# amplifier.net
KiCad netlist of a schematic drawn in EAGLE
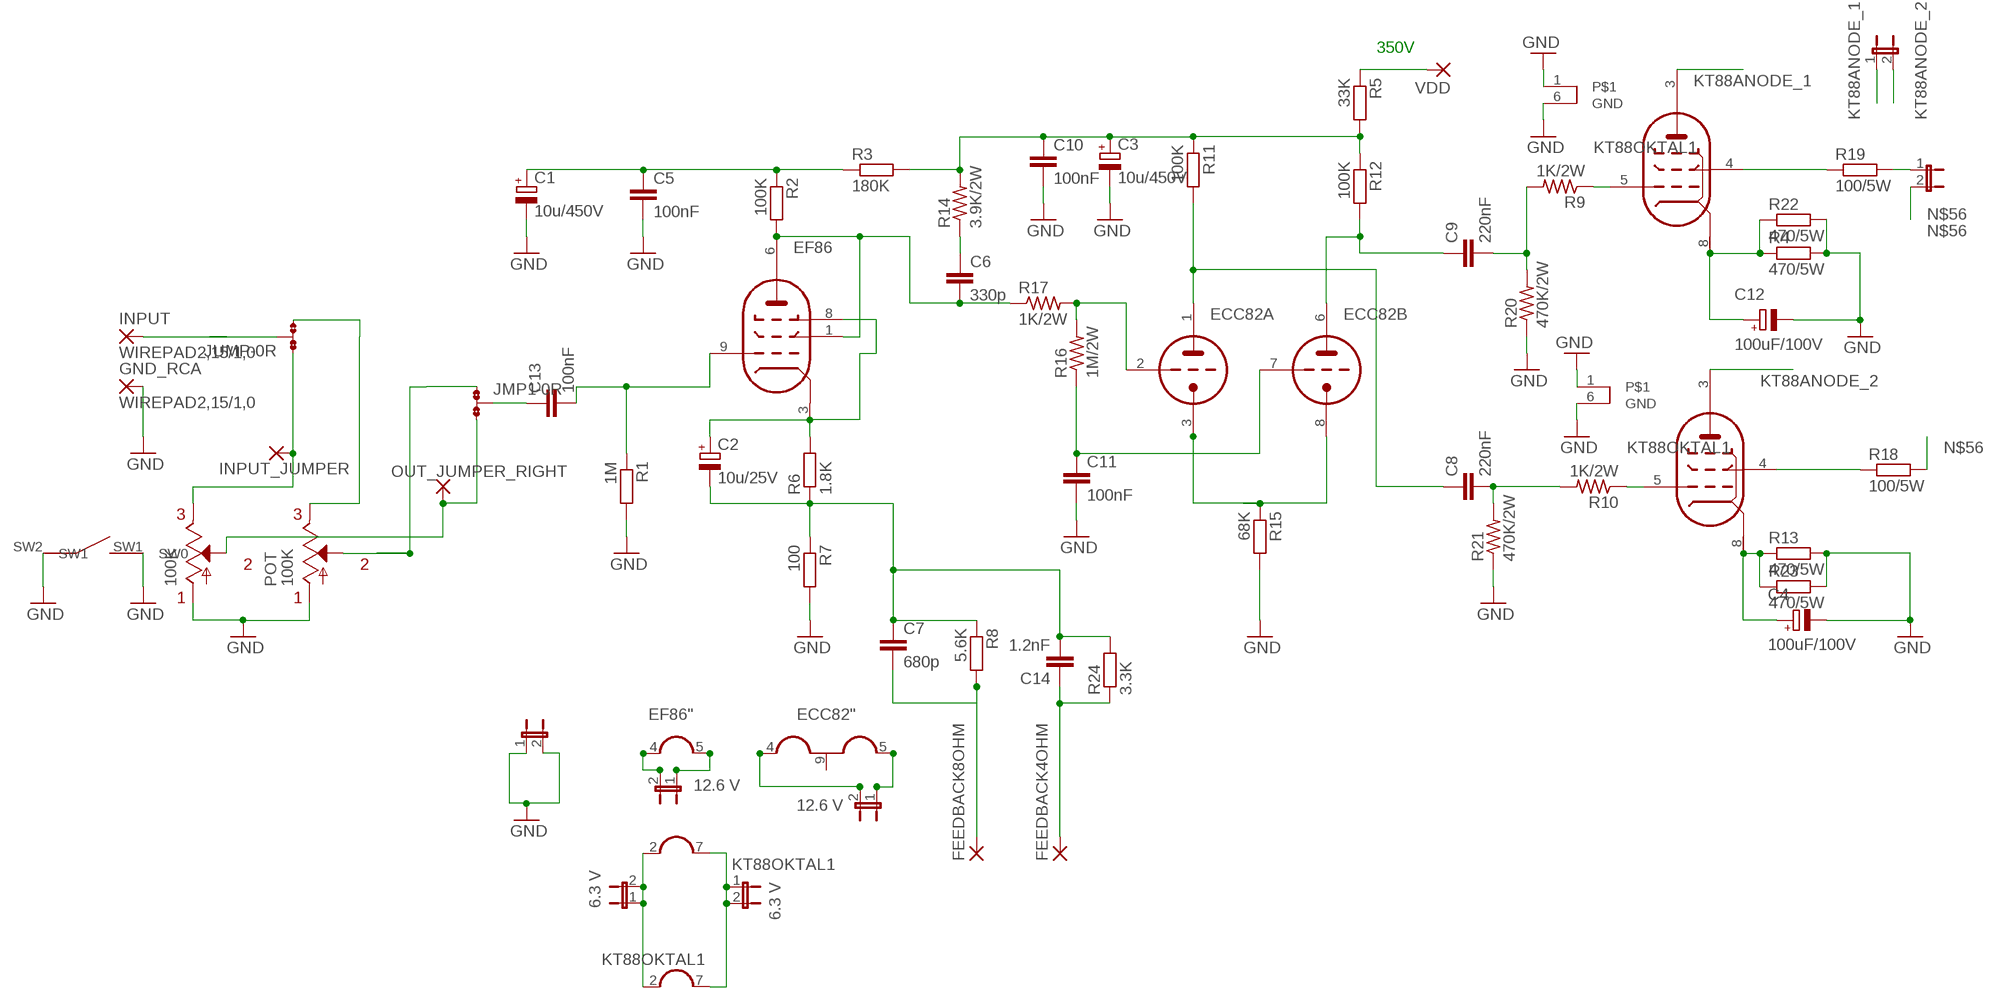
[diagram p0: schematic, sheet 1]

(export (version "E")
  (design (tool "Eeschema 10.0.6"))
  (components
    (comp (ref "6.3_KT88")
      (value "6.3 V")
      (footprint "eagle-import:JP1")
      (libsource (lib "eagle-import") (part "JP1E"))
    )
    (comp (ref "6.3_KTGND")
      (value "6.3 V")
      (footprint "eagle-import:JP1")
      (libsource (lib "eagle-import") (part "JP1E"))
    )
    (comp (ref "12.6V_ECC82")
      (value "12.6 V")
      (footprint "eagle-import:JP1")
      (libsource (lib "eagle-import") (part "JP1E"))
    )
    (comp (ref "12.6_EF86")
      (value "12.6 V")
      (footprint "eagle-import:JP1")
      (libsource (lib "eagle-import") (part "JP1E"))
    )
    (comp (ref "C1")
      (value "10u/450V")
      (footprint "eagle-import:E5-10,5")
      (libsource (lib "eagle-import") (part "CPOL-EUE5-10.5"))
    )
    (comp (ref "C2")
      (value "10u/25V")
      (footprint "eagle-import:E3,5-10")
      (libsource (lib "eagle-import") (part "CPOL-EUE3.5-10"))
    )
    (comp (ref "C3")
      (value "10u/450V")
      (footprint "eagle-import:E5-10,5")
      (libsource (lib "eagle-import") (part "CPOL-EUE5-10.5"))
    )
    (comp (ref "C4")
      (value "100uF/100V")
      (footprint "eagle-import:E3,5-10")
      (libsource (lib "eagle-import") (part "CPOL-EUE3.5-10"))
    )
    (comp (ref "C5")
      (value "100nF")
      (footprint "eagle-import:C7.5B3")
      (libsource (lib "eagle-import") (part "C7.5/3"))
    )
    (comp (ref "C6")
      (value "330p")
      (footprint "eagle-import:C5B5.5")
      (libsource (lib "eagle-import") (part "C5/5.5"))
    )
    (comp (ref "C7")
      (value "680p")
      (footprint "eagle-import:C5B5.5")
      (libsource (lib "eagle-import") (part "C5/5.5"))
    )
    (comp (ref "C8")
      (value "220nF")
      (footprint "eagle-import:C7.5B3")
      (libsource (lib "eagle-import") (part "C7.5/3"))
    )
    (comp (ref "C9")
      (value "220nF")
      (footprint "eagle-import:C7.5B3")
      (libsource (lib "eagle-import") (part "C7.5/3"))
    )
    (comp (ref "C10")
      (value "100nF")
      (footprint "eagle-import:C7.5B3")
      (libsource (lib "eagle-import") (part "C7.5/3"))
    )
    (comp (ref "C11")
      (value "100nF")
      (footprint "eagle-import:C7.5B3")
      (libsource (lib "eagle-import") (part "C7.5/3"))
    )
    (comp (ref "C12")
      (value "100uF/100V")
      (footprint "eagle-import:E3,5-10")
      (libsource (lib "eagle-import") (part "CPOL-EUE3.5-10"))
    )
    (comp (ref "C13")
      (value "100nF")
      (footprint "eagle-import:C0805K")
      (libsource (lib "eagle-import") (part "C-EUC0805K"))
    )
    (comp (ref "C14")
      (value "1.2nF")
      (footprint "eagle-import:C5B5.5")
      (libsource (lib "eagle-import") (part "C5/5.5"))
    )
    (comp (ref "ECC82")
      (value "ECC82-P")
      (footprint "eagle-import:NOVAL")
      (libsource (lib "eagle-import") (part "ECC82-P"))
    )
    (comp (ref "EF86")
      (value "EF86-P")
      (footprint "eagle-import:NOVAL")
      (libsource (lib "eagle-import") (part "EF86-P"))
    )
    (comp (ref "FEEDBACK4OHM")
      (value "2,54/1,1")
      (footprint "eagle-import:2,54_1,1")
      (libsource (lib "eagle-import") (part "2,54/1,1"))
    )
    (comp (ref "FEEDBACK8OHM")
      (value "2,54/1,1")
      (footprint "eagle-import:2,54_1,1")
      (libsource (lib "eagle-import") (part "2,54/1,1"))
    )
    (comp (ref "GND")
      (value "JP1E")
      (footprint "eagle-import:JP1")
      (libsource (lib "eagle-import") (part "JP1E"))
    )
    (comp (ref "GND_RCA")
      (value "WIREPAD2,15/1,0")
      (footprint "eagle-import:2,15_1,0")
      (libsource (lib "eagle-import") (part "WIREPAD2,15/1,0"))
    )
    (comp (ref "INPUT")
      (value "WIREPAD2,15/1,0")
      (footprint "eagle-import:2,15_1,0")
      (libsource (lib "eagle-import") (part "WIREPAD2,15/1,0"))
    )
    (comp (ref "INPUT_JUMPER")
      (value "2,54/1,1")
      (footprint "eagle-import:2,54_1,1")
      (libsource (lib "eagle-import") (part "2,54/1,1"))
    )
    (comp (ref "JMP1")
      (value "0R-JUMPA")
      (footprint "eagle-import:A0R-JMP")
      (libsource (lib "eagle-import") (part "0R-JUMPA"))
    )
    (comp (ref "JUMP")
      (value "0R-JUMPA")
      (footprint "eagle-import:A0R-JMP")
      (libsource (lib "eagle-import") (part "0R-JUMPA"))
    )
    (comp (ref "KT88_OUTPUT")
      (value "JP1E")
      (footprint "eagle-import:JP1")
      (libsource (lib "eagle-import") (part "JP1E"))
    )
    (comp (ref "KT88_TRAFO")
      (value "JP1E")
      (footprint "eagle-import:JP1")
      (libsource (lib "eagle-import") (part "JP1E"))
    )
    (comp (ref "OUT_JUMPER_RIGHT")
      (value "2,54/1,1")
      (footprint "eagle-import:2,54_1,1")
      (libsource (lib "eagle-import") (part "2,54/1,1"))
    )
    (comp (ref "POT")
      (value "100K")
      (footprint "eagle-import:PTR902-2015K-A104")
      (libsource (lib "eagle-import") (part "DUALPOTAUDIO"))
    )
    (comp (ref "R1")
      (value "1M")
      (footprint "eagle-import:R0805")
      (libsource (lib "eagle-import") (part "R-EU_R0805"))
    )
    (comp (ref "R2")
      (value "100K")
      (footprint "eagle-import:R0805")
      (libsource (lib "eagle-import") (part "R-EU_R0805"))
    )
    (comp (ref "R3")
      (value "180K")
      (footprint "eagle-import:R0805")
      (libsource (lib "eagle-import") (part "R-EU_R0805"))
    )
    (comp (ref "R4")
      (value "470/5W")
      (footprint "eagle-import:0617V")
      (libsource (lib "eagle-import") (part "resistor_mod_R-EU_0617/5V"))
    )
    (comp (ref "R5")
      (value "33K")
      (footprint "eagle-import:R0805")
      (libsource (lib "eagle-import") (part "R-EU_R0805"))
    )
    (comp (ref "R6")
      (value "1.8K")
      (footprint "eagle-import:R0805")
      (libsource (lib "eagle-import") (part "R-EU_R0805"))
    )
    (comp (ref "R7")
      (value "100")
      (footprint "eagle-import:R0805")
      (libsource (lib "eagle-import") (part "R-EU_R0805"))
    )
    (comp (ref "R8")
      (value "5.6K")
      (footprint "eagle-import:R0805")
      (libsource (lib "eagle-import") (part "R-EU_R0805"))
    )
    (comp (ref "R9")
      (value "1K/2W")
      (footprint "eagle-import:R2512")
      (libsource (lib "eagle-import") (part "R-US_R2512"))
    )
    (comp (ref "R10")
      (value "1K/2W")
      (footprint "eagle-import:R2512")
      (libsource (lib "eagle-import") (part "R-US_R2512"))
    )
    (comp (ref "R11")
      (value "100K")
      (footprint "eagle-import:R0805")
      (libsource (lib "eagle-import") (part "R-EU_R0805"))
    )
    (comp (ref "R12")
      (value "100K")
      (footprint "eagle-import:R0805")
      (libsource (lib "eagle-import") (part "R-EU_R0805"))
    )
    (comp (ref "R13")
      (value "470/5W")
      (footprint "eagle-import:0617V")
      (libsource (lib "eagle-import") (part "resistor_mod_R-EU_0617/5V"))
    )
    (comp (ref "R14")
      (value "3.9K/2W")
      (footprint "eagle-import:R2512")
      (libsource (lib "eagle-import") (part "R-US_R2512"))
    )
    (comp (ref "R15")
      (value "68K")
      (footprint "eagle-import:R0805")
      (libsource (lib "eagle-import") (part "R-EU_R0805"))
    )
    (comp (ref "R16")
      (value "1M/2W")
      (footprint "eagle-import:R2512")
      (libsource (lib "eagle-import") (part "R-US_R2512"))
    )
    (comp (ref "R17")
      (value "1K/2W")
      (footprint "eagle-import:R2512")
      (libsource (lib "eagle-import") (part "R-US_R2512"))
    )
    (comp (ref "R18")
      (value "100/5W")
      (footprint "eagle-import:P0817V")
      (libsource (lib "eagle-import") (part "R-EU_0817/7V"))
    )
    (comp (ref "R19")
      (value "100/5W")
      (footprint "eagle-import:P0817V")
      (libsource (lib "eagle-import") (part "R-EU_0817/7V"))
    )
    (comp (ref "R20")
      (value "470K/2W")
      (footprint "eagle-import:R2512")
      (libsource (lib "eagle-import") (part "R-US_R2512"))
    )
    (comp (ref "R21")
      (value "470K/2W")
      (footprint "eagle-import:R2512")
      (libsource (lib "eagle-import") (part "R-US_R2512"))
    )
    (comp (ref "R22")
      (value "470/5W")
      (footprint "eagle-import:0617V")
      (libsource (lib "eagle-import") (part "resistor_mod_R-EU_0617/5V"))
    )
    (comp (ref "R23")
      (value "470/5W")
      (footprint "eagle-import:0617V")
      (libsource (lib "eagle-import") (part "resistor_mod_R-EU_0617/5V"))
    )
    (comp (ref "R24")
      (value "3.3K")
      (footprint "eagle-import:R0805")
      (libsource (lib "eagle-import") (part "R-EU_R0805"))
    )
    (comp (ref "U$2")
      (value "KT88OKTAL1")
      (footprint "eagle-import:OKTAL1")
      (libsource (lib "eagle-import") (part "KT88OKTAL1"))
    )
    (comp (ref "U$3")
      (value "KT88OKTAL1")
      (footprint "eagle-import:OKTAL1")
      (libsource (lib "eagle-import") (part "KT88OKTAL1"))
    )
    (comp (ref "VDD")
      (value "2,54/1,1")
      (footprint "eagle-import:2,54_1,1")
      (libsource (lib "eagle-import") (part "2,54/1,1"))
    )
  )
  (nets
    (net (code "1") (name "/KT88ANODE_1") (class "Default")
      (node (ref "KT88_OUTPUT") (pin "1") (pinfunction "1_1") (pintype "passive"))
      (node (ref "U$2") (pin "3") (pinfunction "ANODE_3") (pintype "passive"))
    )
    (net (code "2") (name "/KT88ANODE_2") (class "Default")
      (node (ref "KT88_OUTPUT") (pin "2") (pinfunction "2_2") (pintype "passive"))
      (node (ref "U$3") (pin "3") (pinfunction "ANODE_3") (pintype "passive"))
    )
    (net (code "3") (name "/N$56") (class "Default")
      (node (ref "KT88_TRAFO") (pin "2") (pinfunction "2_2") (pintype "passive"))
      (node (ref "R18") (pin "2") (pinfunction "2_2") (pintype "passive"))
    )
    (net (code "4") (name "GND") (class "Default")
      (node (ref "C1") (pin "-") (pinfunction "-_-") (pintype "passive"))
      (node (ref "C10") (pin "2") (pinfunction "2_2") (pintype "passive"))
      (node (ref "C11") (pin "2") (pinfunction "2_2") (pintype "passive"))
      (node (ref "C12") (pin "-") (pinfunction "-_-") (pintype "passive"))
      (node (ref "C3") (pin "-") (pinfunction "-_-") (pintype "passive"))
      (node (ref "C4") (pin "-") (pinfunction "-_-") (pintype "passive"))
      (node (ref "C5") (pin "2") (pinfunction "2_2") (pintype "passive"))
      (node (ref "GND") (pin "1") (pinfunction "1_1") (pintype "passive"))
      (node (ref "GND") (pin "2") (pinfunction "2_2") (pintype "passive"))
      (node (ref "GND_RCA") (pin "1") (pinfunction "P_1") (pintype "passive"))
      (node (ref "POT") (pin "R1_1") (pinfunction "R1_1_R1_1") (pintype "bidirectional"))
      (node (ref "POT") (pin "R2_1") (pinfunction "R2_1_R2_1") (pintype "bidirectional"))
      (node (ref "POT") (pin "SW1") (pinfunction "SW0_SW1") (pintype "output"))
      (node (ref "POT") (pin "SW2") (pinfunction "SW1_SW2") (pintype "input"))
      (node (ref "R1") (pin "2") (pinfunction "2_2") (pintype "passive"))
      (node (ref "R13") (pin "2") (pinfunction "2_2") (pintype "passive"))
      (node (ref "R15") (pin "2") (pinfunction "2_2") (pintype "passive"))
      (node (ref "R20") (pin "1") (pinfunction "1_1") (pintype "passive"))
      (node (ref "R21") (pin "1") (pinfunction "1_1") (pintype "passive"))
      (node (ref "R22") (pin "2") (pinfunction "2_2") (pintype "passive"))
      (node (ref "R23") (pin "2") (pinfunction "2_2") (pintype "passive"))
      (node (ref "R4") (pin "2") (pinfunction "2_2") (pintype "passive"))
      (node (ref "R7") (pin "2") (pinfunction "2_2") (pintype "passive"))
      (node (ref "U$2") (pin "1") (pinfunction "P$1_1") (pintype "bidirectional"))
      (node (ref "U$2") (pin "6") (pinfunction "GND_6") (pintype "bidirectional"))
      (node (ref "U$3") (pin "1") (pinfunction "P$1_1") (pintype "bidirectional"))
      (node (ref "U$3") (pin "6") (pinfunction "GND_6") (pintype "bidirectional"))
    )
    (net (code "5") (name "Net-(C1-Pad+)") (class "Default")
      (node (ref "C1") (pin "+") (pinfunction "+_+") (pintype "passive"))
      (node (ref "C5") (pin "1") (pinfunction "1_1") (pintype "passive"))
      (node (ref "R2") (pin "1") (pinfunction "1_1") (pintype "passive"))
      (node (ref "R3") (pin "1") (pinfunction "1_1") (pintype "passive"))
    )
    (net (code "6") (name "Net-(C6-Pad1)") (class "Default")
      (node (ref "C6") (pin "1") (pinfunction "1_1") (pintype "passive"))
      (node (ref "R14") (pin "1") (pinfunction "1_1") (pintype "passive"))
    )
    (net (code "7") (name "Net-(C8-Pad2)") (class "Default")
      (node (ref "C8") (pin "2") (pinfunction "2_2") (pintype "passive"))
      (node (ref "R10") (pin "2") (pinfunction "2_2") (pintype "passive"))
      (node (ref "R21") (pin "2") (pinfunction "2_2") (pintype "passive"))
    )
    (net (code "8") (name "Net-(C9-Pad2)") (class "Default")
      (node (ref "C9") (pin "2") (pinfunction "2_2") (pintype "passive"))
      (node (ref "R20") (pin "2") (pinfunction "2_2") (pintype "passive"))
      (node (ref "R9") (pin "2") (pinfunction "2_2") (pintype "passive"))
    )
    (net (code "9") (name "Net-(C10-Pad1)") (class "Default")
      (node (ref "C10") (pin "1") (pinfunction "1_1") (pintype "passive"))
      (node (ref "C3") (pin "+") (pinfunction "+_+") (pintype "passive"))
      (node (ref "R11") (pin "1") (pinfunction "1_1") (pintype "passive"))
      (node (ref "R12") (pin "1") (pinfunction "1_1") (pintype "passive"))
      (node (ref "R14") (pin "2") (pinfunction "2_2") (pintype "passive"))
      (node (ref "R3") (pin "2") (pinfunction "2_2") (pintype "passive"))
      (node (ref "R5") (pin "2") (pinfunction "2_2") (pintype "passive"))
    )
    (net (code "10") (name "Net-(C13-Pad1)") (class "Default")
      (node (ref "C13") (pin "1") (pinfunction "1_1") (pintype "passive"))
      (node (ref "JMP1") (pin "2") (pinfunction "2_2") (pintype "passive"))
    )
    (net (code "11") (name "Net-(C14-Pad2)") (class "Default")
      (node (ref "C14") (pin "2") (pinfunction "2_2") (pintype "passive"))
      (node (ref "C2") (pin "-") (pinfunction "-_-") (pintype "passive"))
      (node (ref "C7") (pin "1") (pinfunction "1_1") (pintype "passive"))
      (node (ref "R24") (pin "2") (pinfunction "2_2") (pintype "passive"))
      (node (ref "R6") (pin "1") (pinfunction "1_1") (pintype "passive"))
      (node (ref "R7") (pin "1") (pinfunction "1_1") (pintype "passive"))
      (node (ref "R8") (pin "1") (pinfunction "1_1") (pintype "passive"))
    )
    (net (code "12") (name "Net-(ECC82A-H1)") (class "Default")
      (node (ref "12.6V_ECC82") (pin "2") (pinfunction "2_2") (pintype "passive"))
      (node (ref "ECC82") (pin "4") (pinfunction "H1_4") (pintype "passive"))
    )
    (net (code "13") (name "Net-(ECC82A-H3)") (class "Default")
      (node (ref "12.6V_ECC82") (pin "1") (pinfunction "1_1") (pintype "passive"))
      (node (ref "ECC82") (pin "5") (pinfunction "H3_5") (pintype "passive"))
    )
    (net (code "14") (name "Net-(ECC82B-TA)") (class "Default")
      (node (ref "C8") (pin "1") (pinfunction "1_1") (pintype "passive"))
      (node (ref "ECC82") (pin "1") (pinfunction "TA_1") (pintype "passive"))
      (node (ref "R11") (pin "2") (pinfunction "2_2") (pintype "passive"))
    )
    (net (code "15") (name "Net-(ECC82B-TG)") (class "Default")
      (node (ref "ECC82") (pin "2") (pinfunction "TG_2") (pintype "passive"))
      (node (ref "R16") (pin "2") (pinfunction "2_2") (pintype "passive"))
      (node (ref "R17") (pin "2") (pinfunction "2_2") (pintype "passive"))
    )
    (net (code "16") (name "Net-(ECC82B-TK)") (class "Default")
      (node (ref "ECC82") (pin "3") (pinfunction "TK_3") (pintype "passive"))
      (node (ref "ECC82") (pin "8") (pinfunction "TK_8") (pintype "passive"))
      (node (ref "R15") (pin "1") (pinfunction "1_1") (pintype "passive"))
    )
    (net (code "17") (name "Net-(ECC82C-TA)") (class "Default")
      (node (ref "C9") (pin "1") (pinfunction "1_1") (pintype "passive"))
      (node (ref "ECC82") (pin "6") (pinfunction "TA_6") (pintype "passive"))
      (node (ref "R12") (pin "2") (pinfunction "2_2") (pintype "passive"))
    )
    (net (code "18") (name "Net-(ECC82C-TG)") (class "Default")
      (node (ref "C11") (pin "1") (pinfunction "1_1") (pintype "passive"))
      (node (ref "ECC82") (pin "7") (pinfunction "TG_7") (pintype "passive"))
      (node (ref "R16") (pin "1") (pinfunction "1_1") (pintype "passive"))
    )
    (net (code "19") (name "Net-(EF86A-H1)") (class "Default")
      (node (ref "12.6_EF86") (pin "2") (pinfunction "2_2") (pintype "passive"))
      (node (ref "EF86") (pin "4") (pinfunction "H1_4") (pintype "passive"))
    )
    (net (code "20") (name "Net-(EF86A-H2)") (class "Default")
      (node (ref "12.6_EF86") (pin "1") (pinfunction "1_1") (pintype "passive"))
      (node (ref "EF86") (pin "5") (pinfunction "H2_5") (pintype "passive"))
    )
    (net (code "21") (name "Net-(EF86B-PA)") (class "Default")
      (node (ref "C6") (pin "2") (pinfunction "2_2") (pintype "passive"))
      (node (ref "EF86") (pin "1") (pinfunction "PSG_1") (pintype "passive"))
      (node (ref "EF86") (pin "6") (pinfunction "PA_6") (pintype "passive"))
      (node (ref "R17") (pin "1") (pinfunction "1_1") (pintype "passive"))
      (node (ref "R2") (pin "2") (pinfunction "2_2") (pintype "passive"))
    )
    (net (code "22") (name "Net-(EF86B-PBG)") (class "Default")
      (node (ref "C2") (pin "+") (pinfunction "+_+") (pintype "passive"))
      (node (ref "EF86") (pin "3") (pinfunction "PK_3") (pintype "passive"))
      (node (ref "EF86") (pin "8") (pinfunction "PBG_8") (pintype "passive"))
      (node (ref "R6") (pin "2") (pinfunction "2_2") (pintype "passive"))
    )
    (net (code "23") (name "Net-(EF86B-PG)") (class "Default")
      (node (ref "C13") (pin "2") (pinfunction "2_2") (pintype "passive"))
      (node (ref "EF86") (pin "9") (pinfunction "PG_9") (pintype "passive"))
      (node (ref "R1") (pin "1") (pinfunction "1_1") (pintype "passive"))
    )
    (net (code "24") (name "Net-(FEEDBACK4OHM-P)") (class "Default")
      (node (ref "C14") (pin "1") (pinfunction "1_1") (pintype "passive"))
      (node (ref "FEEDBACK4OHM") (pin "1") (pinfunction "P_1") (pintype "passive"))
      (node (ref "R24") (pin "1") (pinfunction "1_1") (pintype "passive"))
    )
    (net (code "25") (name "Net-(FEEDBACK8OHM-P)") (class "Default")
      (node (ref "C7") (pin "2") (pinfunction "2_2") (pintype "passive"))
      (node (ref "FEEDBACK8OHM") (pin "1") (pinfunction "P_1") (pintype "passive"))
      (node (ref "R8") (pin "2") (pinfunction "2_2") (pintype "passive"))
    )
    (net (code "26") (name "Net-(INPUT-P)") (class "Default")
      (node (ref "INPUT") (pin "1") (pinfunction "P_1") (pintype "passive"))
      (node (ref "JUMP") (pin "2") (pinfunction "2_2") (pintype "passive"))
    )
    (net (code "27") (name "Net-(INPUT_JUMPER-P)") (class "Default")
      (node (ref "INPUT_JUMPER") (pin "1") (pinfunction "P_1") (pintype "passive"))
      (node (ref "JUMP") (pin "1") (pinfunction "1_1") (pintype "passive"))
      (node (ref "POT") (pin "R2_3") (pinfunction "R2_3_R2_3") (pintype "bidirectional"))
    )
    (net (code "28") (name "Net-(JMP1-Pad1)") (class "Default")
      (node (ref "JMP1") (pin "1") (pinfunction "1_1") (pintype "passive"))
      (node (ref "POT") (pin "R1_2") (pinfunction "R1_2_R1_2") (pintype "bidirectional"))
    )
    (net (code "29") (name "Net-(JUMP-Pad3)") (class "Default")
      (node (ref "JUMP") (pin "3") (pinfunction "3_3") (pintype "passive"))
      (node (ref "POT") (pin "R1_3") (pinfunction "R1_3_R1_3") (pintype "bidirectional"))
    )
    (net (code "30") (name "Net-(KT88_TRAFO-Pad1)") (class "Default")
      (node (ref "KT88_TRAFO") (pin "1") (pinfunction "1_1") (pintype "passive"))
      (node (ref "R19") (pin "2") (pinfunction "2_2") (pintype "passive"))
    )
    (net (code "31") (name "Net-(OUT_JUMPER_RIGHT-P)") (class "Default")
      (node (ref "JMP1") (pin "3") (pinfunction "3_3") (pintype "passive"))
      (node (ref "OUT_JUMPER_RIGHT") (pin "1") (pinfunction "P_1") (pintype "passive"))
      (node (ref "POT") (pin "R2_2") (pinfunction "R2_2_R2_2") (pintype "bidirectional"))
    )
    (net (code "32") (name "Net-(U$2A-H1)") (class "Default")
      (node (ref "6.3_KT88") (pin "1") (pinfunction "1_1") (pintype "passive"))
      (node (ref "6.3_KT88") (pin "2") (pinfunction "2_2") (pintype "passive"))
      (node (ref "U$2") (pin "2") (pinfunction "H1_2") (pintype "passive"))
      (node (ref "U$3") (pin "2") (pinfunction "H1_2") (pintype "passive"))
    )
    (net (code "33") (name "Net-(U$2A-H2)") (class "Default")
      (node (ref "6.3_KTGND") (pin "1") (pinfunction "1_1") (pintype "passive"))
      (node (ref "6.3_KTGND") (pin "2") (pinfunction "2_2") (pintype "passive"))
      (node (ref "U$2") (pin "7") (pinfunction "H2_7") (pintype "passive"))
      (node (ref "U$3") (pin "7") (pinfunction "H2_7") (pintype "passive"))
    )
    (net (code "34") (name "Net-(U$2B-INPUT)") (class "Default")
      (node (ref "R9") (pin "1") (pinfunction "1_1") (pintype "passive"))
      (node (ref "U$2") (pin "5") (pinfunction "INPUT_5") (pintype "passive"))
    )
    (net (code "35") (name "Net-(U$2B-KATHODE)") (class "Default")
      (node (ref "C12") (pin "+") (pinfunction "+_+") (pintype "passive"))
      (node (ref "R22") (pin "1") (pinfunction "1_1") (pintype "passive"))
      (node (ref "R4") (pin "1") (pinfunction "1_1") (pintype "passive"))
      (node (ref "U$2") (pin "8") (pinfunction "KATHODE_8") (pintype "passive"))
    )
    (net (code "36") (name "Net-(U$2B-OUTPUT)") (class "Default")
      (node (ref "R19") (pin "1") (pinfunction "1_1") (pintype "passive"))
      (node (ref "U$2") (pin "4") (pinfunction "OUTPUT_4") (pintype "passive"))
    )
    (net (code "37") (name "Net-(U$3B-INPUT)") (class "Default")
      (node (ref "R10") (pin "1") (pinfunction "1_1") (pintype "passive"))
      (node (ref "U$3") (pin "5") (pinfunction "INPUT_5") (pintype "passive"))
    )
    (net (code "38") (name "Net-(U$3B-KATHODE)") (class "Default")
      (node (ref "C4") (pin "+") (pinfunction "+_+") (pintype "passive"))
      (node (ref "R13") (pin "1") (pinfunction "1_1") (pintype "passive"))
      (node (ref "R23") (pin "1") (pinfunction "1_1") (pintype "passive"))
      (node (ref "U$3") (pin "8") (pinfunction "KATHODE_8") (pintype "passive"))
    )
    (net (code "39") (name "Net-(U$3B-OUTPUT)") (class "Default")
      (node (ref "R18") (pin "1") (pinfunction "1_1") (pintype "passive"))
      (node (ref "U$3") (pin "4") (pinfunction "OUTPUT_4") (pintype "passive"))
    )
    (net (code "40") (name "Net-(VDD-P)") (class "Default")
      (node (ref "R5") (pin "1") (pinfunction "1_1") (pintype "passive"))
      (node (ref "VDD") (pin "1") (pinfunction "P_1") (pintype "passive"))
    )
    (net (code "41") (name "unconnected-(ECC82A-H2-Pad9)") (class "Default")
      (node (ref "ECC82") (pin "9") (pinfunction "H2_9") (pintype "passive"))
    )
  )
)
